# medidor-2.net
KiCad netlist of a schematic drawn in EAGLE
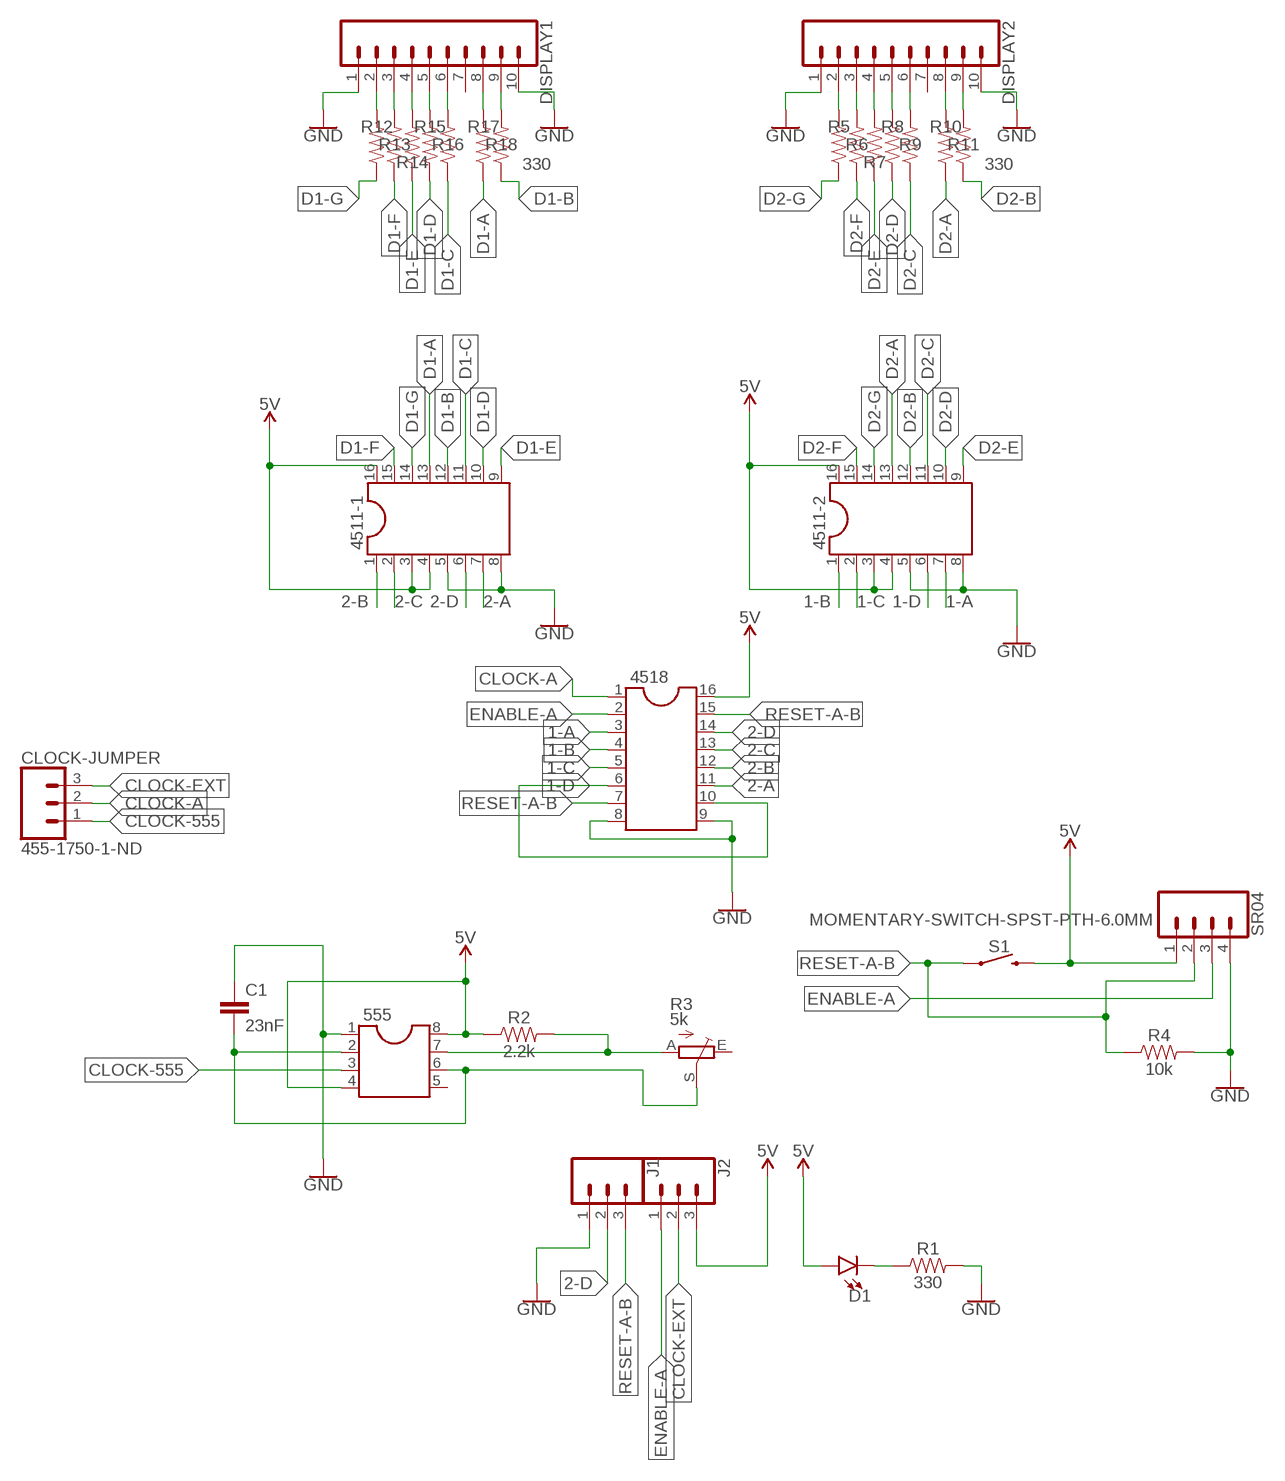
[diagram p0: schematic, sheet 1]

(export (version "E")
  (design (tool "Eeschema 10.0.6"))
  (components
    (comp (ref "555")
      (value "DIL8")
      (footprint "eagle-import:DIL08")
      (libsource (lib "eagle-import") (part "DIL8"))
    )
    (comp (ref "4511-1")
      (value "DIL16")
      (footprint "eagle-import:DIL16")
      (libsource (lib "eagle-import") (part "DIL16"))
    )
    (comp (ref "4511-2")
      (value "DIL16")
      (footprint "eagle-import:DIL16")
      (libsource (lib "eagle-import") (part "DIL16"))
    )
    (comp (ref "4518")
      (value "DIL16")
      (footprint "eagle-import:DIL16")
      (libsource (lib "eagle-import") (part "DIL16"))
    )
    (comp (ref "C1")
      (value "23nF")
      (footprint "eagle-import:C2.5-3")
      (libsource (lib "eagle-import") (part "C2,5-3"))
    )
    (comp (ref "CLOCK-JUMPER")
      (value "455-1750-1-ND")
      (footprint "eagle-import:1X03")
      (libsource (lib "eagle-import") (part "CONN_03"))
    )
    (comp (ref "D1")
      (value "LED5MM")
      (footprint "eagle-import:LED_5MM")
      (libsource (lib "eagle-import") (part "LED5MM"))
    )
    (comp (ref "DISPLAY1")
      (value "CONN_10\"")
      (footprint "eagle-import:1X10")
      (libsource (lib "eagle-import") (part "CONN_10{dblquote}"))
    )
    (comp (ref "DISPLAY2")
      (value "CONN_10\"")
      (footprint "eagle-import:1X10")
      (libsource (lib "eagle-import") (part "CONN_10{dblquote}"))
    )
    (comp (ref "J1")
      (value "CONN_03-SCREW-5MM")
      (footprint "eagle-import:SCREWTERMINAL-5MM-3")
      (libsource (lib "eagle-import") (part "CONN_03-SCREW-5MM"))
    )
    (comp (ref "J2")
      (value "CONN_03-SCREW-5MM")
      (footprint "eagle-import:SCREWTERMINAL-5MM-3")
      (libsource (lib "eagle-import") (part "CONN_03-SCREW-5MM"))
    )
    (comp (ref "R1")
      (value "330")
      (footprint "eagle-import:AXIAL-0.3")
      (libsource (lib "eagle-import") (part "10KOHM-HORIZ-1/4W-5%"))
    )
    (comp (ref "R2")
      (value "2.2k")
      (footprint "eagle-import:AXIAL-0.3")
      (libsource (lib "eagle-import") (part "10KOHM-HORIZ-1/4W-5%"))
    )
    (comp (ref "R3")
      (value "5k")
      (footprint "eagle-import:B25P")
      (libsource (lib "eagle-import") (part "TRIM_EU-B25P"))
    )
    (comp (ref "R4")
      (value "10k")
      (footprint "eagle-import:AXIAL-0.3")
      (libsource (lib "eagle-import") (part "10KOHM-HORIZ-1/4W-5%"))
    )
    (comp (ref "R5")
      (value "330")
      (footprint "eagle-import:AXIAL-0.3")
      (libsource (lib "eagle-import") (part "10KOHM-HORIZ-1/4W-5%"))
    )
    (comp (ref "R6")
      (value "330")
      (footprint "eagle-import:AXIAL-0.3")
      (libsource (lib "eagle-import") (part "10KOHM-HORIZ-1/4W-5%"))
    )
    (comp (ref "R7")
      (value "330")
      (footprint "eagle-import:AXIAL-0.3")
      (libsource (lib "eagle-import") (part "10KOHM-HORIZ-1/4W-5%"))
    )
    (comp (ref "R8")
      (value "330")
      (footprint "eagle-import:AXIAL-0.3")
      (libsource (lib "eagle-import") (part "10KOHM-HORIZ-1/4W-5%"))
    )
    (comp (ref "R9")
      (value "330")
      (footprint "eagle-import:AXIAL-0.3")
      (libsource (lib "eagle-import") (part "10KOHM-HORIZ-1/4W-5%"))
    )
    (comp (ref "R10")
      (value "330")
      (footprint "eagle-import:AXIAL-0.3")
      (libsource (lib "eagle-import") (part "10KOHM-HORIZ-1/4W-5%"))
    )
    (comp (ref "R11")
      (value "330")
      (footprint "eagle-import:AXIAL-0.3")
      (libsource (lib "eagle-import") (part "10KOHM-HORIZ-1/4W-5%"))
    )
    (comp (ref "R12")
      (value "330")
      (footprint "eagle-import:AXIAL-0.3")
      (libsource (lib "eagle-import") (part "10KOHM-HORIZ-1/4W-5%"))
    )
    (comp (ref "R13")
      (value "330")
      (footprint "eagle-import:AXIAL-0.3")
      (libsource (lib "eagle-import") (part "10KOHM-HORIZ-1/4W-5%"))
    )
    (comp (ref "R14")
      (value "330")
      (footprint "eagle-import:AXIAL-0.3")
      (libsource (lib "eagle-import") (part "10KOHM-HORIZ-1/4W-5%"))
    )
    (comp (ref "R15")
      (value "330")
      (footprint "eagle-import:AXIAL-0.3")
      (libsource (lib "eagle-import") (part "10KOHM-HORIZ-1/4W-5%"))
    )
    (comp (ref "R16")
      (value "330")
      (footprint "eagle-import:AXIAL-0.3")
      (libsource (lib "eagle-import") (part "10KOHM-HORIZ-1/4W-5%"))
    )
    (comp (ref "R17")
      (value "330")
      (footprint "eagle-import:AXIAL-0.3")
      (libsource (lib "eagle-import") (part "10KOHM-HORIZ-1/4W-5%"))
    )
    (comp (ref "R18")
      (value "330")
      (footprint "eagle-import:AXIAL-0.3")
      (libsource (lib "eagle-import") (part "10KOHM-HORIZ-1/4W-5%"))
    )
    (comp (ref "S1")
      (value "MOMENTARY-SWITCH-SPST-PTH-6.0MM")
      (footprint "eagle-import:TACTILE_SWITCH_PTH_6.0MM")
      (libsource (lib "eagle-import") (part "MOMENTARY-SWITCH-SPST-PTH-6.0MM"))
    )
    (comp (ref "SR04")
      (value "CONN_04PTH")
      (footprint "eagle-import:1X04")
      (libsource (lib "eagle-import") (part "CONN_04PTH"))
    )
  )
  (nets
    (net (code "1") (name "1-A") (class "Default")
      (node (ref "4511-2") (pin "7") (pinfunction "7_7") (pintype "passive"))
      (node (ref "4518") (pin "3") (pinfunction "3_3") (pintype "passive"))
    )
    (net (code "2") (name "1-B") (class "Default")
      (node (ref "4511-2") (pin "1") (pinfunction "1_1") (pintype "passive"))
      (node (ref "4518") (pin "4") (pinfunction "4_4") (pintype "passive"))
    )
    (net (code "3") (name "1-C") (class "Default")
      (node (ref "4511-2") (pin "2") (pinfunction "2_2") (pintype "passive"))
      (node (ref "4518") (pin "5") (pinfunction "5_5") (pintype "passive"))
    )
    (net (code "4") (name "1-D") (class "Default")
      (node (ref "4511-2") (pin "6") (pinfunction "6_6") (pintype "passive"))
      (node (ref "4518") (pin "10") (pinfunction "10_10") (pintype "passive"))
      (node (ref "4518") (pin "6") (pinfunction "6_6") (pintype "passive"))
    )
    (net (code "5") (name "2-A") (class "Default")
      (node (ref "4511-1") (pin "7") (pinfunction "7_7") (pintype "passive"))
      (node (ref "4518") (pin "11") (pinfunction "11_11") (pintype "passive"))
    )
    (net (code "6") (name "2-B") (class "Default")
      (node (ref "4511-1") (pin "1") (pinfunction "1_1") (pintype "passive"))
      (node (ref "4518") (pin "12") (pinfunction "12_12") (pintype "passive"))
    )
    (net (code "7") (name "2-C") (class "Default")
      (node (ref "4511-1") (pin "2") (pinfunction "2_2") (pintype "passive"))
      (node (ref "4518") (pin "13") (pinfunction "13_13") (pintype "passive"))
    )
    (net (code "8") (name "2-D") (class "Default")
      (node (ref "4511-1") (pin "6") (pinfunction "6_6") (pintype "passive"))
      (node (ref "4518") (pin "14") (pinfunction "14_14") (pintype "passive"))
      (node (ref "J1") (pin "2") (pinfunction "2_2") (pintype "passive"))
    )
    (net (code "9") (name "5V") (class "Default")
      (node (ref "4511-1") (pin "16") (pinfunction "16_16") (pintype "passive"))
      (node (ref "4511-1") (pin "3") (pinfunction "3_3") (pintype "passive"))
      (node (ref "4511-1") (pin "4") (pinfunction "4_4") (pintype "passive"))
      (node (ref "4511-2") (pin "16") (pinfunction "16_16") (pintype "passive"))
      (node (ref "4511-2") (pin "3") (pinfunction "3_3") (pintype "passive"))
      (node (ref "4511-2") (pin "4") (pinfunction "4_4") (pintype "passive"))
      (node (ref "4518") (pin "16") (pinfunction "16_16") (pintype "passive"))
      (node (ref "555") (pin "4") (pinfunction "4_4") (pintype "passive"))
      (node (ref "555") (pin "8") (pinfunction "8_8") (pintype "passive"))
      (node (ref "D1") (pin "A") (pinfunction "A_A") (pintype "passive"))
      (node (ref "J2") (pin "3") (pinfunction "3_3") (pintype "passive"))
      (node (ref "R2") (pin "P$1") (pinfunction "1_P$1") (pintype "passive"))
      (node (ref "S1") (pin "3") (pinfunction "2_3") (pintype "passive"))
      (node (ref "SR04") (pin "1") (pinfunction "1_1") (pintype "passive"))
    )
    (net (code "10") (name "CLOCK-555") (class "Default")
      (node (ref "555") (pin "3") (pinfunction "3_3") (pintype "passive"))
      (node (ref "CLOCK-JUMPER") (pin "1") (pinfunction "1_1") (pintype "passive"))
    )
    (net (code "11") (name "CLOCK-A") (class "Default")
      (node (ref "4518") (pin "1") (pinfunction "1_1") (pintype "passive"))
      (node (ref "CLOCK-JUMPER") (pin "2") (pinfunction "2_2") (pintype "passive"))
    )
    (net (code "12") (name "CLOCK-EXT") (class "Default")
      (node (ref "CLOCK-JUMPER") (pin "3") (pinfunction "3_3") (pintype "passive"))
      (node (ref "J2") (pin "2") (pinfunction "2_2") (pintype "passive"))
    )
    (net (code "13") (name "D1-A") (class "Default")
      (node (ref "4511-1") (pin "13") (pinfunction "13_13") (pintype "passive"))
      (node (ref "R17") (pin "P$1") (pinfunction "1_P$1") (pintype "passive"))
    )
    (net (code "14") (name "D1-B") (class "Default")
      (node (ref "4511-1") (pin "12") (pinfunction "12_12") (pintype "passive"))
      (node (ref "R18") (pin "P$1") (pinfunction "1_P$1") (pintype "passive"))
    )
    (net (code "15") (name "D1-C") (class "Default")
      (node (ref "4511-1") (pin "11") (pinfunction "11_11") (pintype "passive"))
      (node (ref "R16") (pin "P$1") (pinfunction "1_P$1") (pintype "passive"))
    )
    (net (code "16") (name "D1-D") (class "Default")
      (node (ref "4511-1") (pin "10") (pinfunction "10_10") (pintype "passive"))
      (node (ref "R15") (pin "P$1") (pinfunction "1_P$1") (pintype "passive"))
    )
    (net (code "17") (name "D1-E") (class "Default")
      (node (ref "4511-1") (pin "9") (pinfunction "9_9") (pintype "passive"))
      (node (ref "R14") (pin "P$1") (pinfunction "1_P$1") (pintype "passive"))
    )
    (net (code "18") (name "D1-F") (class "Default")
      (node (ref "4511-1") (pin "15") (pinfunction "15_15") (pintype "passive"))
      (node (ref "R13") (pin "P$1") (pinfunction "1_P$1") (pintype "passive"))
    )
    (net (code "19") (name "D1-G") (class "Default")
      (node (ref "4511-1") (pin "14") (pinfunction "14_14") (pintype "passive"))
      (node (ref "R12") (pin "P$1") (pinfunction "1_P$1") (pintype "passive"))
    )
    (net (code "20") (name "D2-A") (class "Default")
      (node (ref "4511-2") (pin "13") (pinfunction "13_13") (pintype "passive"))
      (node (ref "R10") (pin "P$1") (pinfunction "1_P$1") (pintype "passive"))
    )
    (net (code "21") (name "D2-B") (class "Default")
      (node (ref "4511-2") (pin "12") (pinfunction "12_12") (pintype "passive"))
      (node (ref "R11") (pin "P$1") (pinfunction "1_P$1") (pintype "passive"))
    )
    (net (code "22") (name "D2-C") (class "Default")
      (node (ref "4511-2") (pin "11") (pinfunction "11_11") (pintype "passive"))
      (node (ref "R9") (pin "P$1") (pinfunction "1_P$1") (pintype "passive"))
    )
    (net (code "23") (name "D2-D") (class "Default")
      (node (ref "4511-2") (pin "10") (pinfunction "10_10") (pintype "passive"))
      (node (ref "R8") (pin "P$1") (pinfunction "1_P$1") (pintype "passive"))
    )
    (net (code "24") (name "D2-E") (class "Default")
      (node (ref "4511-2") (pin "9") (pinfunction "9_9") (pintype "passive"))
      (node (ref "R7") (pin "P$1") (pinfunction "1_P$1") (pintype "passive"))
    )
    (net (code "25") (name "D2-F") (class "Default")
      (node (ref "4511-2") (pin "15") (pinfunction "15_15") (pintype "passive"))
      (node (ref "R6") (pin "P$1") (pinfunction "1_P$1") (pintype "passive"))
    )
    (net (code "26") (name "D2-G") (class "Default")
      (node (ref "4511-2") (pin "14") (pinfunction "14_14") (pintype "passive"))
      (node (ref "R5") (pin "P$1") (pinfunction "1_P$1") (pintype "passive"))
    )
    (net (code "27") (name "ENABLE-A") (class "Default")
      (node (ref "4518") (pin "2") (pinfunction "2_2") (pintype "passive"))
      (node (ref "J2") (pin "1") (pinfunction "1_1") (pintype "passive"))
      (node (ref "SR04") (pin "3") (pinfunction "3_3") (pintype "passive"))
    )
    (net (code "28") (name "GND") (class "Default")
      (node (ref "4511-1") (pin "5") (pinfunction "5_5") (pintype "passive"))
      (node (ref "4511-1") (pin "8") (pinfunction "8_8") (pintype "passive"))
      (node (ref "4511-2") (pin "5") (pinfunction "5_5") (pintype "passive"))
      (node (ref "4511-2") (pin "8") (pinfunction "8_8") (pintype "passive"))
      (node (ref "4518") (pin "8") (pinfunction "8_8") (pintype "passive"))
      (node (ref "4518") (pin "9") (pinfunction "9_9") (pintype "passive"))
      (node (ref "555") (pin "1") (pinfunction "1_1") (pintype "passive"))
      (node (ref "C1") (pin "1") (pinfunction "1_1") (pintype "passive"))
      (node (ref "DISPLAY1") (pin "1") (pinfunction "1_1") (pintype "passive"))
      (node (ref "DISPLAY1") (pin "10") (pinfunction "10_10") (pintype "passive"))
      (node (ref "DISPLAY2") (pin "1") (pinfunction "1_1") (pintype "passive"))
      (node (ref "DISPLAY2") (pin "10") (pinfunction "10_10") (pintype "passive"))
      (node (ref "J1") (pin "1") (pinfunction "1_1") (pintype "passive"))
      (node (ref "R1") (pin "P$2") (pinfunction "2_P$2") (pintype "passive"))
      (node (ref "R4") (pin "P$2") (pinfunction "2_P$2") (pintype "passive"))
      (node (ref "SR04") (pin "4") (pinfunction "4_4") (pintype "passive"))
    )
    (net (code "29") (name "Net-(555-Pad2)") (class "Default")
      (node (ref "555") (pin "2") (pinfunction "2_2") (pintype "passive"))
      (node (ref "555") (pin "6") (pinfunction "6_6") (pintype "passive"))
      (node (ref "C1") (pin "2") (pinfunction "2_2") (pintype "passive"))
      (node (ref "R3") (pin "S") (pinfunction "S_S") (pintype "passive"))
    )
    (net (code "30") (name "Net-(D1-C)") (class "Default")
      (node (ref "D1") (pin "K") (pinfunction "C_K") (pintype "passive"))
      (node (ref "R1") (pin "P$1") (pinfunction "1_P$1") (pintype "passive"))
    )
    (net (code "31") (name "Net-(R2-2)") (class "Default")
      (node (ref "555") (pin "7") (pinfunction "7_7") (pintype "passive"))
      (node (ref "R2") (pin "P$2") (pinfunction "2_P$2") (pintype "passive"))
      (node (ref "R3") (pin "A") (pinfunction "A_A") (pintype "passive"))
    )
    (net (code "32") (name "Net-(R5-2)") (class "Default")
      (node (ref "DISPLAY2") (pin "2") (pinfunction "2_2") (pintype "passive"))
      (node (ref "R5") (pin "P$2") (pinfunction "2_P$2") (pintype "passive"))
    )
    (net (code "33") (name "Net-(R6-2)") (class "Default")
      (node (ref "DISPLAY2") (pin "3") (pinfunction "3_3") (pintype "passive"))
      (node (ref "R6") (pin "P$2") (pinfunction "2_P$2") (pintype "passive"))
    )
    (net (code "34") (name "Net-(R7-2)") (class "Default")
      (node (ref "DISPLAY2") (pin "4") (pinfunction "4_4") (pintype "passive"))
      (node (ref "R7") (pin "P$2") (pinfunction "2_P$2") (pintype "passive"))
    )
    (net (code "35") (name "Net-(R8-2)") (class "Default")
      (node (ref "DISPLAY2") (pin "5") (pinfunction "5_5") (pintype "passive"))
      (node (ref "R8") (pin "P$2") (pinfunction "2_P$2") (pintype "passive"))
    )
    (net (code "36") (name "Net-(R9-2)") (class "Default")
      (node (ref "DISPLAY2") (pin "6") (pinfunction "6_6") (pintype "passive"))
      (node (ref "R9") (pin "P$2") (pinfunction "2_P$2") (pintype "passive"))
    )
    (net (code "37") (name "Net-(R10-2)") (class "Default")
      (node (ref "DISPLAY2") (pin "8") (pinfunction "8_8") (pintype "passive"))
      (node (ref "R10") (pin "P$2") (pinfunction "2_P$2") (pintype "passive"))
    )
    (net (code "38") (name "Net-(R11-2)") (class "Default")
      (node (ref "DISPLAY2") (pin "9") (pinfunction "9_9") (pintype "passive"))
      (node (ref "R11") (pin "P$2") (pinfunction "2_P$2") (pintype "passive"))
    )
    (net (code "39") (name "Net-(R12-2)") (class "Default")
      (node (ref "DISPLAY1") (pin "2") (pinfunction "2_2") (pintype "passive"))
      (node (ref "R12") (pin "P$2") (pinfunction "2_P$2") (pintype "passive"))
    )
    (net (code "40") (name "Net-(R13-2)") (class "Default")
      (node (ref "DISPLAY1") (pin "3") (pinfunction "3_3") (pintype "passive"))
      (node (ref "R13") (pin "P$2") (pinfunction "2_P$2") (pintype "passive"))
    )
    (net (code "41") (name "Net-(R14-2)") (class "Default")
      (node (ref "DISPLAY1") (pin "4") (pinfunction "4_4") (pintype "passive"))
      (node (ref "R14") (pin "P$2") (pinfunction "2_P$2") (pintype "passive"))
    )
    (net (code "42") (name "Net-(R15-2)") (class "Default")
      (node (ref "DISPLAY1") (pin "5") (pinfunction "5_5") (pintype "passive"))
      (node (ref "R15") (pin "P$2") (pinfunction "2_P$2") (pintype "passive"))
    )
    (net (code "43") (name "Net-(R16-2)") (class "Default")
      (node (ref "DISPLAY1") (pin "6") (pinfunction "6_6") (pintype "passive"))
      (node (ref "R16") (pin "P$2") (pinfunction "2_P$2") (pintype "passive"))
    )
    (net (code "44") (name "Net-(R17-2)") (class "Default")
      (node (ref "DISPLAY1") (pin "8") (pinfunction "8_8") (pintype "passive"))
      (node (ref "R17") (pin "P$2") (pinfunction "2_P$2") (pintype "passive"))
    )
    (net (code "45") (name "Net-(R18-2)") (class "Default")
      (node (ref "DISPLAY1") (pin "9") (pinfunction "9_9") (pintype "passive"))
      (node (ref "R18") (pin "P$2") (pinfunction "2_P$2") (pintype "passive"))
    )
    (net (code "46") (name "RESET-A-B") (class "Default")
      (node (ref "4518") (pin "15") (pinfunction "15_15") (pintype "passive"))
      (node (ref "4518") (pin "7") (pinfunction "7_7") (pintype "passive"))
      (node (ref "J1") (pin "3") (pinfunction "3_3") (pintype "passive"))
      (node (ref "R4") (pin "P$1") (pinfunction "1_P$1") (pintype "passive"))
      (node (ref "S1") (pin "1") (pinfunction "1_1") (pintype "passive"))
      (node (ref "SR04") (pin "2") (pinfunction "2_2") (pintype "passive"))
    )
    (net (code "47") (name "unconnected-(555-Pad5)") (class "Default")
      (node (ref "555") (pin "5") (pinfunction "5_5") (pintype "passive"))
    )
    (net (code "48") (name "unconnected-(DISPLAY1-Pad7)") (class "Default")
      (node (ref "DISPLAY1") (pin "7") (pinfunction "7_7") (pintype "passive"))
    )
    (net (code "49") (name "unconnected-(DISPLAY2-Pad7)") (class "Default")
      (node (ref "DISPLAY2") (pin "7") (pinfunction "7_7") (pintype "passive"))
    )
    (net (code "50") (name "unconnected-(R3-PadE)") (class "Default")
      (node (ref "R3") (pin "E") (pinfunction "E_E") (pintype "passive"))
    )
  )
)
